# BusAndInterfaceDesign.net
KiCad netlist of a schematic drawn in Altium Designer
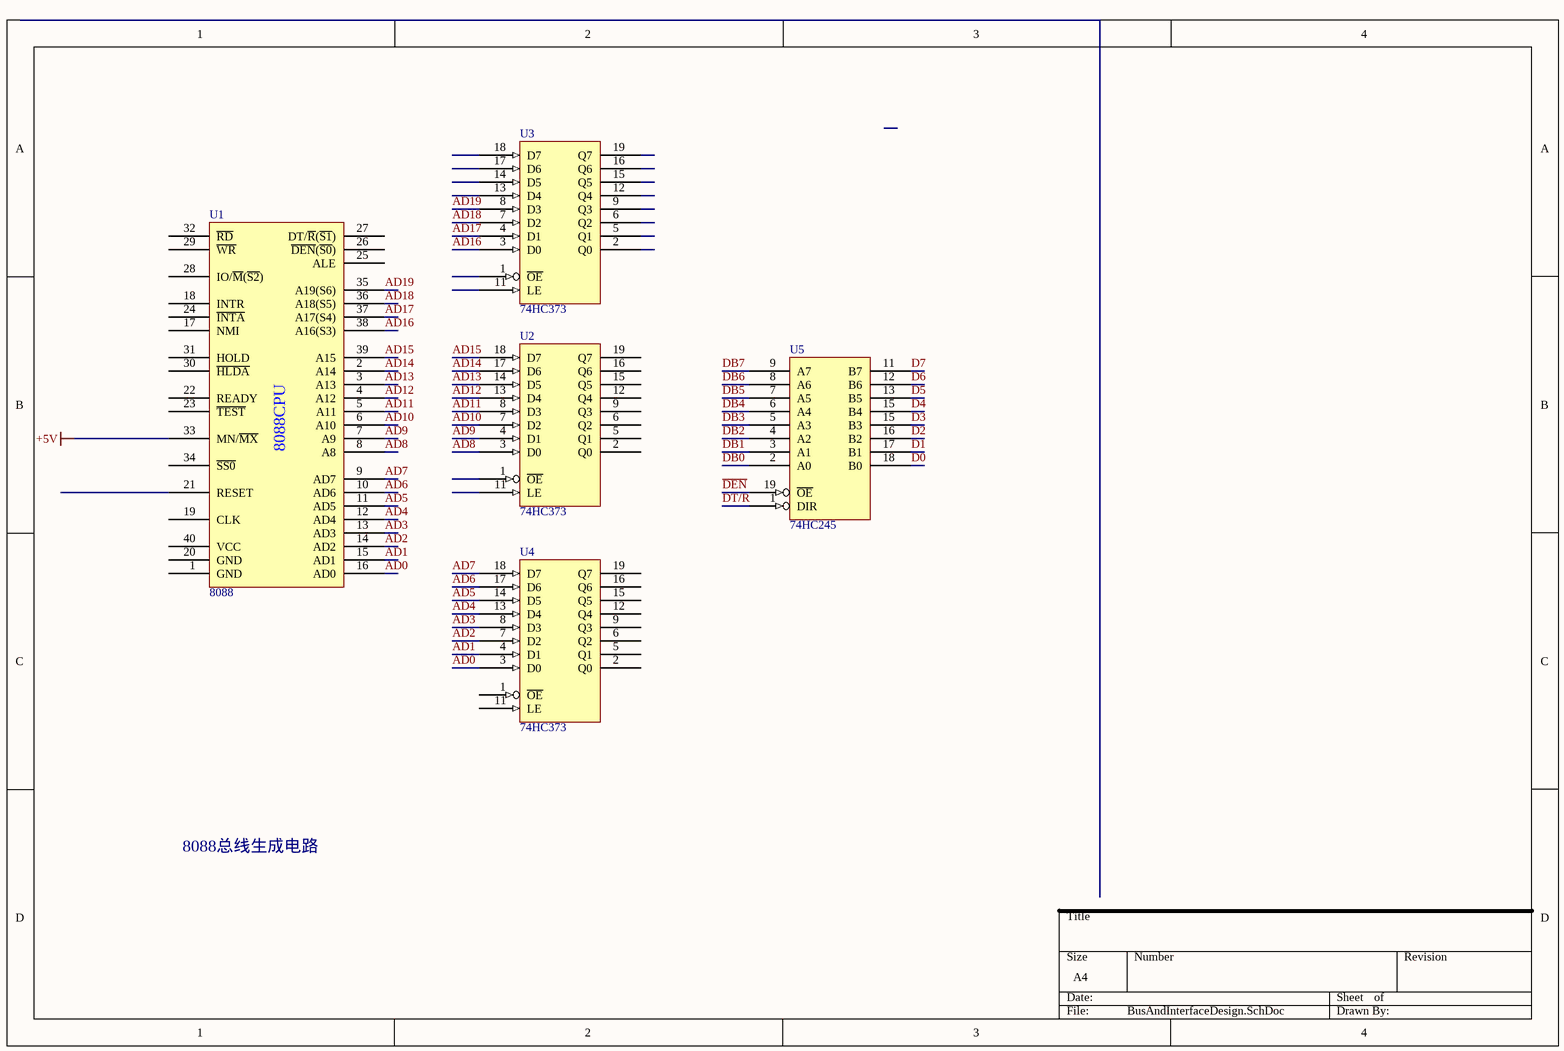
[diagram p0: BusAndInterfaceDesign.SchDoc]

(export (version "E")
  (design (tool "Eeschema 10.0.6"))
  (components
    (comp (ref "U1") (value "8088") (libsource (lib "8088ThreeBuses") (part "8088")))
    (comp (ref "U2") (value "74HC373") (libsource (lib "8088ThreeBuses") (part "74HC373")))
    (comp (ref "U3") (value "74HC373") (libsource (lib "8088ThreeBuses") (part "74HC373")))
    (comp (ref "U4") (value "74HC373") (libsource (lib "8088ThreeBuses") (part "74HC373")))
    (comp (ref "U5") (value "74HC245") (libsource (lib "8088ThreeBuses") (part "74HC245")))
  )
  (nets
    (net (code "1") (name "+5V") (class "Default")
      (node (ref "U1") (pin "33") (pinfunction "MN/~{MX}_33") (pintype "passive"))
    )
    (net (code "2") (name "/AD0") (class "Default")
      (node (ref "U1") (pin "16") (pinfunction "AD0_16") (pintype "passive"))
      (node (ref "U4") (pin "3") (pinfunction "D0_3") (pintype "input"))
    )
    (net (code "3") (name "/AD1") (class "Default")
      (node (ref "U1") (pin "15") (pinfunction "AD1_15") (pintype "passive"))
      (node (ref "U4") (pin "4") (pinfunction "D1_4") (pintype "input"))
    )
    (net (code "4") (name "/AD2") (class "Default")
      (node (ref "U1") (pin "14") (pinfunction "AD2_14") (pintype "passive"))
      (node (ref "U4") (pin "7") (pinfunction "D2_7") (pintype "input"))
    )
    (net (code "5") (name "/AD3") (class "Default")
      (node (ref "U1") (pin "13") (pinfunction "AD3_13") (pintype "passive"))
      (node (ref "U4") (pin "8") (pinfunction "D3_8") (pintype "input"))
    )
    (net (code "6") (name "/AD4") (class "Default")
      (node (ref "U1") (pin "12") (pinfunction "AD4_12") (pintype "passive"))
      (node (ref "U4") (pin "13") (pinfunction "D4_13") (pintype "input"))
    )
    (net (code "7") (name "/AD5") (class "Default")
      (node (ref "U1") (pin "11") (pinfunction "AD5_11") (pintype "passive"))
      (node (ref "U4") (pin "14") (pinfunction "D5_14") (pintype "input"))
    )
    (net (code "8") (name "/AD6") (class "Default")
      (node (ref "U1") (pin "10") (pinfunction "AD6_10") (pintype "passive"))
      (node (ref "U4") (pin "17") (pinfunction "D6_17") (pintype "input"))
    )
    (net (code "9") (name "/AD7") (class "Default")
      (node (ref "U1") (pin "9") (pinfunction "AD7_9") (pintype "passive"))
      (node (ref "U4") (pin "18") (pinfunction "D7_18") (pintype "input"))
    )
    (net (code "10") (name "/AD8") (class "Default")
      (node (ref "U1") (pin "8") (pinfunction "A8_8") (pintype "passive"))
      (node (ref "U2") (pin "3") (pinfunction "D0_3") (pintype "input"))
    )
    (net (code "11") (name "/AD9") (class "Default")
      (node (ref "U1") (pin "7") (pinfunction "A9_7") (pintype "passive"))
      (node (ref "U2") (pin "4") (pinfunction "D1_4") (pintype "input"))
    )
    (net (code "12") (name "/AD10") (class "Default")
      (node (ref "U1") (pin "6") (pinfunction "A10_6") (pintype "passive"))
      (node (ref "U2") (pin "7") (pinfunction "D2_7") (pintype "input"))
    )
    (net (code "13") (name "/AD11") (class "Default")
      (node (ref "U1") (pin "5") (pinfunction "A11_5") (pintype "passive"))
      (node (ref "U2") (pin "8") (pinfunction "D3_8") (pintype "input"))
    )
    (net (code "14") (name "/AD12") (class "Default")
      (node (ref "U1") (pin "4") (pinfunction "A12_4") (pintype "passive"))
      (node (ref "U2") (pin "13") (pinfunction "D4_13") (pintype "input"))
    )
    (net (code "15") (name "/AD13") (class "Default")
      (node (ref "U1") (pin "3") (pinfunction "A13_3") (pintype "passive"))
      (node (ref "U2") (pin "14") (pinfunction "D5_14") (pintype "input"))
    )
    (net (code "16") (name "/AD14") (class "Default")
      (node (ref "U1") (pin "2") (pinfunction "A14_2") (pintype "passive"))
      (node (ref "U2") (pin "17") (pinfunction "D6_17") (pintype "input"))
    )
    (net (code "17") (name "/AD15") (class "Default")
      (node (ref "U1") (pin "39") (pinfunction "A15_39") (pintype "passive"))
      (node (ref "U2") (pin "18") (pinfunction "D7_18") (pintype "input"))
    )
    (net (code "18") (name "/AD16") (class "Default")
      (node (ref "U1") (pin "38") (pinfunction "A16(S3)_38") (pintype "passive"))
      (node (ref "U3") (pin "3") (pinfunction "D0_3") (pintype "input"))
    )
    (net (code "19") (name "/AD17") (class "Default")
      (node (ref "U1") (pin "37") (pinfunction "A17(S4)_37") (pintype "passive"))
      (node (ref "U3") (pin "4") (pinfunction "D1_4") (pintype "input"))
    )
    (net (code "20") (name "/AD18") (class "Default")
      (node (ref "U1") (pin "36") (pinfunction "A18(S5)_36") (pintype "passive"))
      (node (ref "U3") (pin "7") (pinfunction "D2_7") (pintype "input"))
    )
    (net (code "21") (name "/AD19") (class "Default")
      (node (ref "U1") (pin "35") (pinfunction "A19(S6)_35") (pintype "passive"))
      (node (ref "U3") (pin "8") (pinfunction "D3_8") (pintype "input"))
    )
    (net (code "22") (name "/D0") (class "Default")
      (node (ref "U5") (pin "18") (pinfunction "B0_18") (pintype "tri_state"))
    )
    (net (code "23") (name "/D1") (class "Default")
      (node (ref "U5") (pin "17") (pinfunction "B1_17") (pintype "tri_state"))
    )
    (net (code "24") (name "/D2") (class "Default")
      (node (ref "U5") (pin "16") (pinfunction "B2_16") (pintype "tri_state"))
    )
    (net (code "25") (name "/D3") (class "Default")
      (node (ref "U5") (pin "15") (pinfunction "B3_15") (pintype "tri_state"))
    )
    (net (code "26") (name "/D4") (class "Default")
      (node (ref "U5") (pin "15") (pinfunction "B4_15") (pintype "tri_state"))
    )
    (net (code "27") (name "/D5") (class "Default")
      (node (ref "U5") (pin "13") (pinfunction "B5_13") (pintype "tri_state"))
    )
    (net (code "28") (name "/D6") (class "Default")
      (node (ref "U5") (pin "12") (pinfunction "B6_12") (pintype "tri_state"))
    )
    (net (code "29") (name "/D7") (class "Default")
      (node (ref "U5") (pin "11") (pinfunction "B7_11") (pintype "tri_state"))
    )
    (net (code "30") (name "/DB0") (class "Default")
      (node (ref "U5") (pin "2") (pinfunction "A0_2") (pintype "passive"))
    )
    (net (code "31") (name "/DB1") (class "Default")
      (node (ref "U5") (pin "3") (pinfunction "A1_3") (pintype "passive"))
    )
    (net (code "32") (name "/DB2") (class "Default")
      (node (ref "U5") (pin "4") (pinfunction "A2_4") (pintype "passive"))
    )
    (net (code "33") (name "/DB3") (class "Default")
      (node (ref "U5") (pin "5") (pinfunction "A3_5") (pintype "passive"))
    )
    (net (code "34") (name "/DB4") (class "Default")
      (node (ref "U5") (pin "6") (pinfunction "A4_6") (pintype "passive"))
    )
    (net (code "35") (name "/DB5") (class "Default")
      (node (ref "U5") (pin "7") (pinfunction "A5_7") (pintype "passive"))
    )
    (net (code "36") (name "/DB6") (class "Default")
      (node (ref "U5") (pin "8") (pinfunction "A6_8") (pintype "passive"))
    )
    (net (code "37") (name "/DB7") (class "Default")
      (node (ref "U5") (pin "9") (pinfunction "A7_9") (pintype "passive"))
    )
    (net (code "38") (name "/DT{slash}~{R}") (class "Default")
      (node (ref "U5") (pin "1") (pinfunction "DIR_1") (pintype "input"))
    )
    (net (code "39") (name "/~{DEN}") (class "Default")
      (node (ref "U5") (pin "19") (pinfunction "~{OE}_19") (pintype "input"))
    )
    (net (code "40") (name "unconnected-(U1-ALE-Pad25)") (class "Default")
      (node (ref "U1") (pin "25") (pinfunction "ALE_25") (pintype "passive"))
    )
    (net (code "41") (name "unconnected-(U1-CLK-Pad19)") (class "Default")
      (node (ref "U1") (pin "19") (pinfunction "CLK_19") (pintype "passive"))
    )
    (net (code "42") (name "unconnected-(U1-DT{slash}~{R}(~{S1})-Pad27)") (class "Default")
      (node (ref "U1") (pin "27") (pinfunction "DT/~{R}(~{S1})_27") (pintype "passive"))
    )
    (net (code "43") (name "unconnected-(U1-GND-Pad1)") (class "Default")
      (node (ref "U1") (pin "1") (pinfunction "GND_1") (pintype "passive"))
    )
    (net (code "44") (name "unconnected-(U1-GND-Pad20)") (class "Default")
      (node (ref "U1") (pin "20") (pinfunction "GND_20") (pintype "passive"))
    )
    (net (code "45") (name "unconnected-(U1-HOLD-Pad31)") (class "Default")
      (node (ref "U1") (pin "31") (pinfunction "HOLD_31") (pintype "passive"))
    )
    (net (code "46") (name "unconnected-(U1-INTR-Pad18)") (class "Default")
      (node (ref "U1") (pin "18") (pinfunction "INTR_18") (pintype "passive"))
    )
    (net (code "47") (name "unconnected-(U1-IO{slash}~{M}(~{S2})-Pad28)") (class "Default")
      (node (ref "U1") (pin "28") (pinfunction "IO/~{M}(~{S2})_28") (pintype "passive"))
    )
    (net (code "48") (name "unconnected-(U1-NMI-Pad17)") (class "Default")
      (node (ref "U1") (pin "17") (pinfunction "NMI_17") (pintype "passive"))
    )
    (net (code "49") (name "unconnected-(U1-READY-Pad22)") (class "Default")
      (node (ref "U1") (pin "22") (pinfunction "READY_22") (pintype "passive"))
    )
    (net (code "50") (name "unconnected-(U1-RESET-Pad21)") (class "Default")
      (node (ref "U1") (pin "21") (pinfunction "RESET_21") (pintype "passive"))
    )
    (net (code "51") (name "unconnected-(U1-VCC-Pad40)") (class "Default")
      (node (ref "U1") (pin "40") (pinfunction "VCC_40") (pintype "passive"))
    )
    (net (code "52") (name "unconnected-(U1-~{DEN}(~{S0})-Pad26)") (class "Default")
      (node (ref "U1") (pin "26") (pinfunction "~{DEN}(~{S0})_26") (pintype "passive"))
    )
    (net (code "53") (name "unconnected-(U1-~{HLDA}-Pad30)") (class "Default")
      (node (ref "U1") (pin "30") (pinfunction "~{HLDA}_30") (pintype "passive"))
    )
    (net (code "54") (name "unconnected-(U1-~{INTA}-Pad24)") (class "Default")
      (node (ref "U1") (pin "24") (pinfunction "~{INTA}_24") (pintype "passive"))
    )
    (net (code "55") (name "unconnected-(U1-~{RD}-Pad32)") (class "Default")
      (node (ref "U1") (pin "32") (pinfunction "~{RD}_32") (pintype "passive"))
    )
    (net (code "56") (name "unconnected-(U1-~{SS0}-Pad34)") (class "Default")
      (node (ref "U1") (pin "34") (pinfunction "~{SS0}_34") (pintype "passive"))
    )
    (net (code "57") (name "unconnected-(U1-~{TEST}-Pad23)") (class "Default")
      (node (ref "U1") (pin "23") (pinfunction "~{TEST}_23") (pintype "passive"))
    )
    (net (code "58") (name "unconnected-(U1-~{WR}-Pad29)") (class "Default")
      (node (ref "U1") (pin "29") (pinfunction "~{WR}_29") (pintype "passive"))
    )
    (net (code "59") (name "unconnected-(U2-LE-Pad11)") (class "Default")
      (node (ref "U2") (pin "11") (pinfunction "LE_11") (pintype "input"))
    )
    (net (code "60") (name "unconnected-(U2-Q0-Pad2)") (class "Default")
      (node (ref "U2") (pin "2") (pinfunction "Q0_2") (pintype "tri_state"))
    )
    (net (code "61") (name "unconnected-(U2-Q1-Pad5)") (class "Default")
      (node (ref "U2") (pin "5") (pinfunction "Q1_5") (pintype "tri_state"))
    )
    (net (code "62") (name "unconnected-(U2-Q2-Pad6)") (class "Default")
      (node (ref "U2") (pin "6") (pinfunction "Q2_6") (pintype "tri_state"))
    )
    (net (code "63") (name "unconnected-(U2-Q3-Pad9)") (class "Default")
      (node (ref "U2") (pin "9") (pinfunction "Q3_9") (pintype "tri_state"))
    )
    (net (code "64") (name "unconnected-(U2-Q4-Pad12)") (class "Default")
      (node (ref "U2") (pin "12") (pinfunction "Q4_12") (pintype "tri_state"))
    )
    (net (code "65") (name "unconnected-(U2-Q5-Pad15)") (class "Default")
      (node (ref "U2") (pin "15") (pinfunction "Q5_15") (pintype "tri_state"))
    )
    (net (code "66") (name "unconnected-(U2-Q6-Pad16)") (class "Default")
      (node (ref "U2") (pin "16") (pinfunction "Q6_16") (pintype "tri_state"))
    )
    (net (code "67") (name "unconnected-(U2-Q7-Pad19)") (class "Default")
      (node (ref "U2") (pin "19") (pinfunction "Q7_19") (pintype "tri_state"))
    )
    (net (code "68") (name "unconnected-(U2-~{OE}-Pad1)") (class "Default")
      (node (ref "U2") (pin "1") (pinfunction "~{OE}_1") (pintype "input"))
    )
    (net (code "69") (name "unconnected-(U3-D4-Pad13)") (class "Default")
      (node (ref "U3") (pin "13") (pinfunction "D4_13") (pintype "input"))
    )
    (net (code "70") (name "unconnected-(U3-D5-Pad14)") (class "Default")
      (node (ref "U3") (pin "14") (pinfunction "D5_14") (pintype "input"))
    )
    (net (code "71") (name "unconnected-(U3-D6-Pad17)") (class "Default")
      (node (ref "U3") (pin "17") (pinfunction "D6_17") (pintype "input"))
    )
    (net (code "72") (name "unconnected-(U3-D7-Pad18)") (class "Default")
      (node (ref "U3") (pin "18") (pinfunction "D7_18") (pintype "input"))
    )
    (net (code "73") (name "unconnected-(U3-LE-Pad11)") (class "Default")
      (node (ref "U3") (pin "11") (pinfunction "LE_11") (pintype "input"))
    )
    (net (code "74") (name "unconnected-(U3-Q0-Pad2)") (class "Default")
      (node (ref "U3") (pin "2") (pinfunction "Q0_2") (pintype "tri_state"))
    )
    (net (code "75") (name "unconnected-(U3-Q1-Pad5)") (class "Default")
      (node (ref "U3") (pin "5") (pinfunction "Q1_5") (pintype "tri_state"))
    )
    (net (code "76") (name "unconnected-(U3-Q2-Pad6)") (class "Default")
      (node (ref "U3") (pin "6") (pinfunction "Q2_6") (pintype "tri_state"))
    )
    (net (code "77") (name "unconnected-(U3-Q3-Pad9)") (class "Default")
      (node (ref "U3") (pin "9") (pinfunction "Q3_9") (pintype "tri_state"))
    )
    (net (code "78") (name "unconnected-(U3-Q4-Pad12)") (class "Default")
      (node (ref "U3") (pin "12") (pinfunction "Q4_12") (pintype "tri_state"))
    )
    (net (code "79") (name "unconnected-(U3-Q5-Pad15)") (class "Default")
      (node (ref "U3") (pin "15") (pinfunction "Q5_15") (pintype "tri_state"))
    )
    (net (code "80") (name "unconnected-(U3-Q6-Pad16)") (class "Default")
      (node (ref "U3") (pin "16") (pinfunction "Q6_16") (pintype "tri_state"))
    )
    (net (code "81") (name "unconnected-(U3-Q7-Pad19)") (class "Default")
      (node (ref "U3") (pin "19") (pinfunction "Q7_19") (pintype "tri_state"))
    )
    (net (code "82") (name "unconnected-(U3-~{OE}-Pad1)") (class "Default")
      (node (ref "U3") (pin "1") (pinfunction "~{OE}_1") (pintype "input"))
    )
    (net (code "83") (name "unconnected-(U4-LE-Pad11)") (class "Default")
      (node (ref "U4") (pin "11") (pinfunction "LE_11") (pintype "input"))
    )
    (net (code "84") (name "unconnected-(U4-Q0-Pad2)") (class "Default")
      (node (ref "U4") (pin "2") (pinfunction "Q0_2") (pintype "tri_state"))
    )
    (net (code "85") (name "unconnected-(U4-Q1-Pad5)") (class "Default")
      (node (ref "U4") (pin "5") (pinfunction "Q1_5") (pintype "tri_state"))
    )
    (net (code "86") (name "unconnected-(U4-Q2-Pad6)") (class "Default")
      (node (ref "U4") (pin "6") (pinfunction "Q2_6") (pintype "tri_state"))
    )
    (net (code "87") (name "unconnected-(U4-Q3-Pad9)") (class "Default")
      (node (ref "U4") (pin "9") (pinfunction "Q3_9") (pintype "tri_state"))
    )
    (net (code "88") (name "unconnected-(U4-Q4-Pad12)") (class "Default")
      (node (ref "U4") (pin "12") (pinfunction "Q4_12") (pintype "tri_state"))
    )
    (net (code "89") (name "unconnected-(U4-Q5-Pad15)") (class "Default")
      (node (ref "U4") (pin "15") (pinfunction "Q5_15") (pintype "tri_state"))
    )
    (net (code "90") (name "unconnected-(U4-Q6-Pad16)") (class "Default")
      (node (ref "U4") (pin "16") (pinfunction "Q6_16") (pintype "tri_state"))
    )
    (net (code "91") (name "unconnected-(U4-Q7-Pad19)") (class "Default")
      (node (ref "U4") (pin "19") (pinfunction "Q7_19") (pintype "tri_state"))
    )
    (net (code "92") (name "unconnected-(U4-~{OE}-Pad1)") (class "Default")
      (node (ref "U4") (pin "1") (pinfunction "~{OE}_1") (pintype "input"))
    )
  )
)
